# flyback.net
KiCad netlist of a schematic drawn in Altium Designer
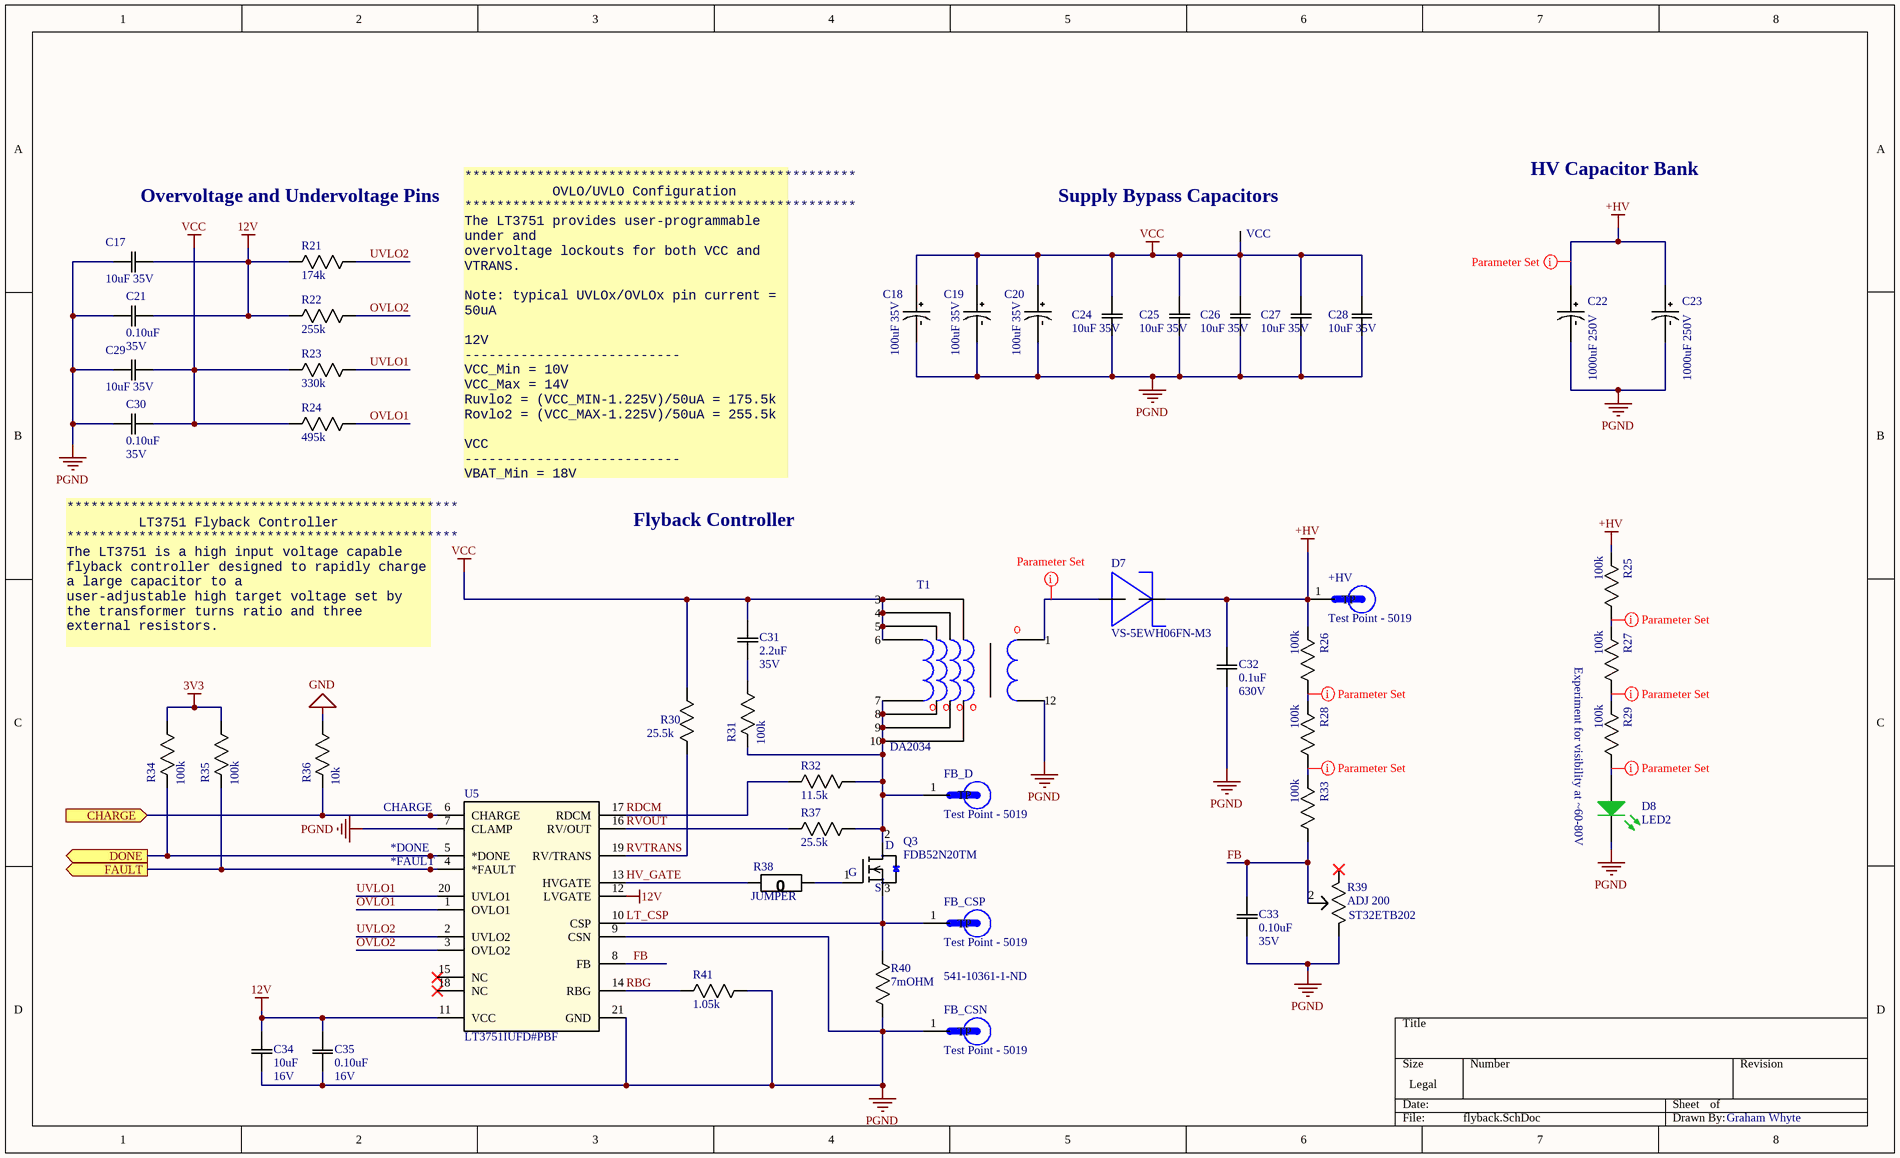
[diagram p0: flyback.SchDoc]

(export (version "E")
  (design (tool "Eeschema 10.0.6"))
  (components
    (comp (ref "*DONE")
      (value "Test Point (Via)")
      (footprint "TP")
      (libsource (lib "AltiumLibraries") (part "Test Point (Via)"))
    )
    (comp (ref "*FAULT")
      (value "Test Point (Via)")
      (footprint "TP")
      (libsource (lib "AltiumLibraries") (part "Test Point (Via)"))
    )
    (comp (ref "+HV")
      (value "Test Point - 5019")
      (footprint "TP380X203")
      (description "PC Test Point, Miniature Phosphor Bronze, Silver Plating Surface Mount Mounting Type")
      (fields (field (name "MP") "5019") (field (name "MF") "Keystone Electronics"))
      (libsource (lib "AltiumLibraries") (part "Test Point - 5019"))
    )
    (comp (ref "C17")
      (value "10uF 35V")
      (footprint "0805")
      (description "CAP CER 10uF 35V X5R 1206/0805")
      (fields (field (name "TOLERANCE") "10%"))
      (libsource (lib "AltiumLibraries") (part "CAP 10uF 35V"))
    )
    (comp (ref "C18")
      (value "100uF 35V")
      (footprint "CAP POL ALU 6.3x5.8")
      (description "CAP ALUM 100UF 35V SMD")
      (fields (field (name "TOLERANCE") "20%"))
      (libsource (lib "AltiumLibraries") (part "CAP POL 100uF SMD"))
    )
    (comp (ref "C19")
      (value "100uF 35V")
      (footprint "CAP POL ALU 6.3x5.8")
      (description "CAP ALUM 100UF 35V SMD")
      (fields (field (name "TOLERANCE") "20%"))
      (libsource (lib "AltiumLibraries") (part "CAP POL 100uF SMD"))
    )
    (comp (ref "C20")
      (value "100uF 35V")
      (footprint "CAP POL ALU 6.3x5.8")
      (description "CAP ALUM 100UF 35V SMD")
      (fields (field (name "TOLERANCE") "20%"))
      (libsource (lib "AltiumLibraries") (part "CAP POL 100uF SMD"))
    )
    (comp (ref "C21")
      (value "0.10uF")
      (footprint "0805")
      (description "CAP CER 0.10UF 35V X7R 0603/0805")
      (fields (field (name "TOLERANCE") "10%") (field (name "RATING") "35V"))
      (libsource (lib "AltiumLibraries") (part "CAP 0.10uF 35V"))
    )
    (comp (ref "C22")
      (value "1000uF 250V")
      (footprint "RADIAL, CAN - THRU 25.4mm")
      (description "United Chemi-Con\r\nESMQ251VSN102MQ45S")
      (fields
        (field (name "MANUFACTURER") "United Chemi-Con")
        (field (name "MANUFACTURER PART NUMBER") "ESMQ251VSN102MQ45S")
      )
      (libsource (lib "AltiumLibraries") (part "CAP POL 1000uF"))
    )
    (comp (ref "C23")
      (value "1000uF 250V")
      (footprint "RADIAL, CAN - THRU 25.4mm")
      (description "United Chemi-Con\r\nESMQ251VSN102MQ45S")
      (fields
        (field (name "MANUFACTURER") "United Chemi-Con")
        (field (name "MANUFACTURER PART NUMBER") "ESMQ251VSN102MQ45S")
      )
      (libsource (lib "AltiumLibraries") (part "CAP POL 1000uF"))
    )
    (comp (ref "C24")
      (value "10uF 35V")
      (footprint "0805")
      (description "CAP CER 10uF 35V X5R 1206/0805")
      (fields (field (name "TOLERANCE") "10%"))
      (libsource (lib "AltiumLibraries") (part "CAP 10uF 35V"))
    )
    (comp (ref "C25")
      (value "10uF 35V")
      (footprint "0805")
      (description "CAP CER 10uF 35V X5R 1206/0805")
      (fields (field (name "TOLERANCE") "10%"))
      (libsource (lib "AltiumLibraries") (part "CAP 10uF 35V"))
    )
    (comp (ref "C26")
      (value "10uF 35V")
      (footprint "0805")
      (description "CAP CER 10uF 35V X5R 1206/0805")
      (fields (field (name "TOLERANCE") "10%"))
      (libsource (lib "AltiumLibraries") (part "CAP 10uF 35V"))
    )
    (comp (ref "C27")
      (value "10uF 35V")
      (footprint "0805")
      (description "CAP CER 10uF 35V X5R 1206/0805")
      (fields (field (name "TOLERANCE") "10%"))
      (libsource (lib "AltiumLibraries") (part "CAP 10uF 35V"))
    )
    (comp (ref "C28")
      (value "10uF 35V")
      (footprint "0805")
      (description "CAP CER 10uF 35V X5R 1206/0805")
      (fields (field (name "TOLERANCE") "10%"))
      (libsource (lib "AltiumLibraries") (part "CAP 10uF 35V"))
    )
    (comp (ref "C29")
      (value "10uF 35V")
      (footprint "0805")
      (description "CAP CER 10uF 35V X5R 1206/0805")
      (fields (field (name "TOLERANCE") "10%"))
      (libsource (lib "AltiumLibraries") (part "CAP 10uF 35V"))
    )
    (comp (ref "C30")
      (value "0.10uF")
      (footprint "0805")
      (description "CAP CER 0.10UF 35V X7R 0603/0805")
      (fields (field (name "TOLERANCE") "10%") (field (name "RATING") "35V"))
      (libsource (lib "AltiumLibraries") (part "CAP 0.10uF 35V"))
    )
    (comp (ref "C31")
      (value "2.2uF")
      (footprint "0603")
      (description "CAP CER 2.2UF 35V X7R 0603/0805")
      (fields (field (name "TOLERANCE") "10%") (field (name "RATING") "35V"))
      (libsource (lib "AltiumLibraries") (part "CAP 2.2uF 35V"))
    )
    (comp (ref "C32")
      (value "0.1uF")
      (footprint "1210")
      (description "CAP CER 0.1uF 630V X7R 1210")
      (fields (field (name "TOLERANCE") "10%") (field (name "RATING") "630V"))
      (libsource (lib "AltiumLibraries") (part "CAP 0.1uF 630V"))
    )
    (comp (ref "C33")
      (value "0.10uF")
      (footprint "0805")
      (description "CAP CER 0.10UF 35V X7R 0603/0805")
      (fields (field (name "TOLERANCE") "10%") (field (name "RATING") "35V"))
      (libsource (lib "AltiumLibraries") (part "CAP 0.10uF 35V"))
    )
    (comp (ref "C34")
      (value "10uF")
      (footprint "0603")
      (description "CAP CER 10UF 16V X5R 0603/0805")
      (fields (field (name "TOLERANCE") "10%") (field (name "RATING") "16V"))
      (libsource (lib "AltiumLibraries") (part "CAP 10uF 16V"))
    )
    (comp (ref "C35")
      (value "0.10uF")
      (footprint "0603")
      (description "CAP CER 0.10UF 16V X5R 0603/0805")
      (fields (field (name "TOLERANCE") "10%") (field (name "RATING") "16V"))
      (libsource (lib "AltiumLibraries") (part "CAP 0.10uF 16V"))
    )
    (comp (ref "CHARGE")
      (value "Test Point (Via)")
      (footprint "TP")
      (libsource (lib "AltiumLibraries") (part "Test Point (Via)"))
    )
    (comp (ref "D7")
      (value "VS-5EWH06FN-M3")
      (footprint "DPAK (TO-252)")
      (description "Diode Switching 600V 5A DPAK")
      (fields (field (name "MF") "Vishay Diodes"))
      (libsource (lib "AltiumLibraries") (part "VS-5EWH06FN-M3"))
    )
    (comp (ref "D8")
      (value "LED2")
      (footprint "3.2X1.6X1.1")
      (description "Typical RED, GREEN, YELLOW, AMBER GaAs LED")
      (libsource (lib "AltiumLibraries") (part "LED GREEN SMD"))
    )
    (comp (ref "FB_CSN")
      (value "Test Point - 5019")
      (footprint "TP380X203")
      (description "PC Test Point, Miniature Phosphor Bronze, Silver Plating Surface Mount Mounting Type")
      (fields (field (name "MP") "5019") (field (name "MF") "Keystone Electronics"))
      (libsource (lib "AltiumLibraries") (part "Test Point - 5019"))
    )
    (comp (ref "FB_CSP")
      (value "Test Point - 5019")
      (footprint "TP380X203")
      (description "PC Test Point, Miniature Phosphor Bronze, Silver Plating Surface Mount Mounting Type")
      (fields (field (name "MP") "5019") (field (name "MF") "Keystone Electronics"))
      (libsource (lib "AltiumLibraries") (part "Test Point - 5019"))
    )
    (comp (ref "FB_D")
      (value "Test Point - 5019")
      (footprint "TP380X203")
      (description "PC Test Point, Miniature Phosphor Bronze, Silver Plating Surface Mount Mounting Type")
      (fields (field (name "MP") "5019") (field (name "MF") "Keystone Electronics"))
      (libsource (lib "AltiumLibraries") (part "Test Point - 5019"))
    )
    (comp (ref "Q3")
      (value "FDB52N20TM")
      (footprint "D2PAK (TO-263) (2)")
      (description "N-Channel 200 V 52A (Tc) 357W (Tc) Surface Mount D²PAK (TO-263)")
      (libsource (lib "AltiumLibraries") (part "MOSFET N-CH FDB52N20TM"))
    )
    (comp (ref "R21")
      (value "174k")
      (footprint "0603")
      (description "RES SMD 174K OHM 1% 1/8W 0805/0603")
      (fields
        (field (name "MANUFACTURER") "Yageo")
        (field (name "MANUFACTURER PART NUMBER") "RC0805FR-07174KL")
      )
      (libsource (lib "AltiumLibraries") (part "RES 174k 1/8W"))
    )
    (comp (ref "R22")
      (value "255k")
      (footprint "0603")
      (description "0805/0603 Resistor, 6A, 0.125W, 25ppm, 0.1%, 255K")
      (libsource (lib "AltiumLibraries") (part "RES 255k 1/8W - 5%"))
    )
    (comp (ref "R23")
      (value "330k")
      (footprint "0603")
      (description "RES SMD 330K OHM 1% 1/8W 0805/0603")
      (libsource (lib "AltiumLibraries") (part "RES 330k 1/8W - 1%"))
    )
    (comp (ref "R24")
      (value "495k")
      (footprint "0603")
      (description "RES SMD 495K OHM 1% 1/8W 0805/0603")
      (fields
        (field (name "MANUFACTURER") "Yageo")
        (field (name "MANUFACTURER PART NUMBER") "RC0805FR-07499KL")
      )
      (libsource (lib "AltiumLibraries") (part "RES 495k 1/8W"))
    )
    (comp (ref "R25")
      (value "100k")
      (footprint "0603")
      (description "RES SMD 100K OHM 5% 1/8W 0805/0603")
      (fields (field (name "TOLERANCE") "5%"))
      (libsource (lib "") (part "RES 100k 1/8W - 5%_1"))
    )
    (comp (ref "R26")
      (value "100k")
      (footprint "0603")
      (description "RES SMD 100K OHM 1% 1/8W 0805/0603")
      (fields (field (name "TOLERANCE") "1%"))
      (libsource (lib "AltiumLibraries") (part "RES 100k 1/8W - 1%"))
    )
    (comp (ref "R27")
      (value "100k")
      (footprint "0603")
      (description "RES SMD 100K OHM 5% 1/8W 0805/0603")
      (fields (field (name "TOLERANCE") "5%"))
      (libsource (lib "AltiumLibraries") (part "RES 100k 1/8W - 5%"))
    )
    (comp (ref "R28")
      (value "100k")
      (footprint "0603")
      (description "RES SMD 100K OHM 1% 1/8W 0805/0603")
      (fields (field (name "TOLERANCE") "1%"))
      (libsource (lib "") (part "RES 100k 1/8W - 1%_1"))
    )
    (comp (ref "R29")
      (value "100k")
      (footprint "0603")
      (description "RES SMD 100K OHM 5% 1/8W 0805/0603")
      (fields (field (name "TOLERANCE") "5%"))
      (libsource (lib "AltiumLibraries") (part "RES 100k 1/8W - 5%"))
    )
    (comp (ref "R30")
      (value "25.5k")
      (footprint "0603")
      (description "RES SMD 25.5K OHM 0.1% 1/8W 0805/0603")
      (fields
        (field (name "MANUFACTURER") "Panasonic")
        (field (name "MANUFACTURER PART NUMBER") "ERA-6AEB2552V")
      )
      (libsource (lib "AltiumLibraries") (part "RES 25.5k 1/8W"))
    )
    (comp (ref "R31")
      (value "100k")
      (footprint "0603")
      (description "RES SMD 100K OHM 1% 1/8W 0805/0603")
      (fields (field (name "TOLERANCE") "1%"))
      (libsource (lib "AltiumLibraries") (part "RES 100k 1/8W - 1%"))
    )
    (comp (ref "R32")
      (value "11.5k")
      (footprint "0603")
      (description "RES SMD 11.5K OHM 0.1% 1/8W 0805 Thin Film")
      (fields
        (field (name "MANUFACTURER") "Panasonic")
        (field (name "MANUFACTURER PART NUMBER") "ERA-6AEB1152V")
      )
      (libsource (lib "AltiumLibraries") (part "RES 11.5k 1/8W"))
    )
    (comp (ref "R33")
      (value "100k")
      (footprint "0603")
      (description "RES SMD 100K OHM 1% 1/8W 0805/0603")
      (fields (field (name "TOLERANCE") "1%"))
      (libsource (lib "") (part "RES 100k 1/8W - 1%_1"))
    )
    (comp (ref "R34")
      (value "100k")
      (footprint "0603")
      (description "RES SMD 100K OHM 5% 1/8W 0805/0603")
      (fields (field (name "TOLERANCE") "5%"))
      (libsource (lib "AltiumLibraries") (part "RES 100k 1/8W - 5%"))
    )
    (comp (ref "R35")
      (value "100k")
      (footprint "0603")
      (description "RES SMD 100K OHM 5% 1/8W 0805/0603")
      (fields (field (name "TOLERANCE") "5%"))
      (libsource (lib "AltiumLibraries") (part "RES 100k 1/8W - 5%"))
    )
    (comp (ref "R36")
      (value "10k")
      (footprint "0603")
      (description "RES SMD 10K OHM 5% 1/8W 0805/0603")
      (fields (field (name "TOLERANCE") "5%"))
      (libsource (lib "AltiumLibraries") (part "RES 10k 1/8W - 5%"))
    )
    (comp (ref "R37")
      (value "25.5k")
      (footprint "0603")
      (description "RES SMD 25.5K OHM 0.1% 1/8W 0805/0603")
      (fields
        (field (name "MANUFACTURER") "Panasonic")
        (field (name "MANUFACTURER PART NUMBER") "ERA-6AEB2552V")
      )
      (libsource (lib "AltiumLibraries") (part "RES 25.5k 1/8W"))
    )
    (comp (ref "R38")
      (value "JUMPER")
      (footprint "0603")
      (description "RES SMD 0 OHM JUMPER GENERIC 0805/0603")
      (libsource (lib "AltiumLibraries") (part "RES 0 JUMPER"))
    )
    (comp (ref "R39")
      (value "ADJ 200")
      (footprint "POT SMD")
      (description "SMD Potentiometer 200Ohm Range")
      (libsource (lib "AltiumLibraries") (part "RES POT 200"))
    )
    (comp (ref "R40")
      (value "7mOHM")
      (footprint "2512")
      (description "RES SMD 7m OHM 1% 3W 2512")
      (fields
        (field (name "TOLERANCE") "1%")
        (field (name "MFG") "VISHAY")
        (field (name "SUPPLIER PART NUMBER 1") "541-10361-1-ND")
      )
      (libsource (lib "AltiumLibraries") (part "RES 7m 3W"))
    )
    (comp (ref "R41")
      (value "1.05k")
      (footprint "0603")
      (description "RES SMD 1.05K OHM 0.1% 1/8W 0805/0603")
      (fields (field (name "TOLERANCE") "0.1%"))
      (libsource (lib "AltiumLibraries") (part "RES 1.05k 1/8W"))
    )
    (comp (ref "T1")
      (value "DA2034")
      (footprint "DA2034")
      (description "Audio Transformers / Signal Transformers DA2032 Cap Chrgr For Linear LT3750/51")
      (libsource (lib "AltiumLibraries") (part "DA2034"))
    )
    (comp (ref "U5")
      (value "LT3751IUFD#PBF")
      (footprint "QFN-20_UFD_LIT-M")
      (description "Photoflash Capacitor Charger PMIC 20-QFN (4x5)")
      (fields
        (field (name "MANUFACTURER_PART_NUMBER") "lt3751iufd#pbf")
        (field (name "COPYRIGHT") "Copyright (C) 2021 Ultra Librarian. All rights reserved.")
      )
      (libsource (lib "AltiumLibraries") (part "LT3751IUFD#PBF"))
    )
    (comp (ref "VCC")
      (value "Test Point (Via)")
      (footprint "TP")
      (libsource (lib "AltiumLibraries") (part "Test Point (Via)"))
    )
  )
  (nets
    (net (code "1") (name "+HV") (class "Default")
      (node (ref "+HV") (pin "1") (pinfunction "TP_1") (pintype "passive"))
      (node (ref "C22") (pin "POS") (pinfunction "POS_POS") (pintype "passive"))
      (node (ref "C23") (pin "POS") (pinfunction "POS_POS") (pintype "passive"))
      (node (ref "C32") (pin "1") (pinfunction "C1_1") (pintype "passive"))
      (node (ref "D7") (pin "OUT") (pinfunction "OUT_OUT") (pintype "passive"))
      (node (ref "R25") (pin "2") (pinfunction "R2_2") (pintype "passive"))
      (node (ref "R26") (pin "2") (pinfunction "R2_2") (pintype "passive"))
    )
    (net (code "3") (name "/CHARGE") (class "Default")
      (node (ref "CHARGE") (pin "1") (pinfunction "1_1") (pintype "passive"))
      (node (ref "R36") (pin "2") (pinfunction "R2_2") (pintype "passive"))
      (node (ref "U5") (pin "6") (pinfunction "CHARGE_6") (pintype "passive"))
    )
    (net (code "4") (name "/DONE") (class "Default")
      (node (ref "*DONE") (pin "1") (pinfunction "1_1") (pintype "passive"))
      (node (ref "R34") (pin "2") (pinfunction "R2_2") (pintype "passive"))
      (node (ref "U5") (pin "5") (pinfunction "*DONE_5") (pintype "passive"))
    )
    (net (code "5") (name "/FAULT") (class "Default")
      (node (ref "*FAULT") (pin "1") (pinfunction "1_1") (pintype "passive"))
      (node (ref "R35") (pin "2") (pinfunction "R2_2") (pintype "passive"))
      (node (ref "U5") (pin "4") (pinfunction "*FAULT_4") (pintype "passive"))
    )
    (net (code "6") (name "/FB") (class "Default")
      (node (ref "C33") (pin "1") (pinfunction "C1_1") (pintype "passive"))
      (node (ref "R33") (pin "1") (pinfunction "R1_1") (pintype "passive"))
      (node (ref "R39") (pin "2") (pinfunction "2_2") (pintype "passive"))
      (node (ref "U5") (pin "8") (pinfunction "FB_8") (pintype "passive"))
    )
    (net (code "7") (name "/HV_GATE") (class "Default")
      (node (ref "R38") (pin "2") (pinfunction "R2_2") (pintype "passive"))
      (node (ref "U5") (pin "13") (pinfunction "HVGATE_13") (pintype "passive"))
    )
    (net (code "8") (name "/LT_CSP") (class "Default")
      (node (ref "FB_CSP") (pin "1") (pinfunction "TP_1") (pintype "passive"))
      (node (ref "Q3") (pin "3") (pinfunction "S_3") (pintype "passive"))
      (node (ref "R40") (pin "2") (pinfunction "R2_2") (pintype "passive"))
      (node (ref "U5") (pin "10") (pinfunction "CSP_10") (pintype "passive"))
    )
    (net (code "9") (name "/OVLO1") (class "Default")
      (node (ref "R24") (pin "1") (pinfunction "R1_1") (pintype "passive"))
      (node (ref "U5") (pin "1") (pinfunction "OVLO1_1") (pintype "passive"))
    )
    (net (code "10") (name "/OVLO2") (class "Default")
      (node (ref "R22") (pin "1") (pinfunction "R1_1") (pintype "passive"))
      (node (ref "U5") (pin "3") (pinfunction "OVLO2_3") (pintype "passive"))
    )
    (net (code "11") (name "/RBG") (class "Default")
      (node (ref "R41") (pin "2") (pinfunction "R2_2") (pintype "passive"))
      (node (ref "U5") (pin "14") (pinfunction "RBG_14") (pintype "passive"))
    )
    (net (code "12") (name "/RDCM") (class "Default")
      (node (ref "R32") (pin "2") (pinfunction "R2_2") (pintype "passive"))
      (node (ref "U5") (pin "17") (pinfunction "RDCM_17") (pintype "passive"))
    )
    (net (code "13") (name "/RVOUT") (class "Default")
      (node (ref "R37") (pin "2") (pinfunction "R2_2") (pintype "passive"))
      (node (ref "U5") (pin "16") (pinfunction "RV/OUT_16") (pintype "passive"))
    )
    (net (code "14") (name "/RVTRANS") (class "Default")
      (node (ref "R30") (pin "2") (pinfunction "R2_2") (pintype "passive"))
      (node (ref "U5") (pin "19") (pinfunction "RV/TRANS_19") (pintype "passive"))
    )
    (net (code "15") (name "/UVLO1") (class "Default")
      (node (ref "R23") (pin "1") (pinfunction "R1_1") (pintype "passive"))
      (node (ref "U5") (pin "20") (pinfunction "UVLO1_20") (pintype "passive"))
    )
    (net (code "16") (name "/UVLO2") (class "Default")
      (node (ref "R21") (pin "1") (pinfunction "R1_1") (pintype "passive"))
      (node (ref "U5") (pin "2") (pinfunction "UVLO2_2") (pintype "passive"))
    )
    (net (code "17") (name "3V3") (class "Default")
      (node (ref "R34") (pin "1") (pinfunction "R1_1") (pintype "passive"))
      (node (ref "R35") (pin "1") (pinfunction "R1_1") (pintype "passive"))
    )
    (net (code "18") (name "12V") (class "Default")
      (node (ref "C17") (pin "2") (pinfunction "C2_2") (pintype "passive"))
      (node (ref "C21") (pin "2") (pinfunction "C2_2") (pintype "passive"))
      (node (ref "C34") (pin "1") (pinfunction "C1_1") (pintype "passive"))
      (node (ref "C35") (pin "2") (pinfunction "C2_2") (pintype "passive"))
      (node (ref "R21") (pin "2") (pinfunction "R2_2") (pintype "passive"))
      (node (ref "R22") (pin "2") (pinfunction "R2_2") (pintype "passive"))
      (node (ref "U5") (pin "11") (pinfunction "VCC_11") (pintype "power_in"))
      (node (ref "U5") (pin "12") (pinfunction "LVGATE_12") (pintype "passive"))
    )
    (net (code "19") (name "GND") (class "Default")
      (node (ref "R36") (pin "1") (pinfunction "R1_1") (pintype "passive"))
    )
    (net (code "20") (name "Net-(C31-C1)") (class "Default")
      (node (ref "C31") (pin "1") (pinfunction "C1_1") (pintype "passive"))
      (node (ref "R31") (pin "1") (pinfunction "R1_1") (pintype "passive"))
    )
    (net (code "21") (name "Net-(D7-PadIN)") (class "Default")
      (node (ref "D7") (pin "IN") (pinfunction "IN_IN") (pintype "passive"))
      (node (ref "T1") (pin "1") (pinfunction "1_1") (pintype "passive"))
    )
    (net (code "22") (name "Net-(D8-A)") (class "Default")
      (node (ref "D8") (pin "1") (pinfunction "A_1") (pintype "passive"))
      (node (ref "R29") (pin "1") (pinfunction "R1_1") (pintype "passive"))
    )
    (net (code "23") (name "Net-(FB_D-TP)") (class "Default")
      (node (ref "FB_D") (pin "1") (pinfunction "TP_1") (pintype "passive"))
      (node (ref "Q3") (pin "2") (pinfunction "D_2") (pintype "passive"))
      (node (ref "R31") (pin "2") (pinfunction "R2_2") (pintype "passive"))
      (node (ref "R32") (pin "1") (pinfunction "R1_1") (pintype "passive"))
      (node (ref "R37") (pin "1") (pinfunction "R1_1") (pintype "passive"))
      (node (ref "T1") (pin "10") (pinfunction "10_10") (pintype "passive"))
      (node (ref "T1") (pin "7") (pinfunction "7_7") (pintype "passive"))
      (node (ref "T1") (pin "8") (pinfunction "8_8") (pintype "passive"))
      (node (ref "T1") (pin "9") (pinfunction "9_9") (pintype "passive"))
    )
    (net (code "24") (name "Net-(Q3-G)") (class "Default")
      (node (ref "Q3") (pin "1") (pinfunction "G_1") (pintype "passive"))
      (node (ref "R38") (pin "1") (pinfunction "R1_1") (pintype "passive"))
    )
    (net (code "25") (name "Net-(R25-R1)") (class "Default")
      (node (ref "R25") (pin "1") (pinfunction "R1_1") (pintype "passive"))
      (node (ref "R27") (pin "2") (pinfunction "R2_2") (pintype "passive"))
    )
    (net (code "26") (name "Net-(R26-R1)") (class "Default")
      (node (ref "R26") (pin "1") (pinfunction "R1_1") (pintype "passive"))
      (node (ref "R28") (pin "2") (pinfunction "R2_2") (pintype "passive"))
    )
    (net (code "27") (name "Net-(R27-R1)") (class "Default")
      (node (ref "R27") (pin "1") (pinfunction "R1_1") (pintype "passive"))
      (node (ref "R29") (pin "2") (pinfunction "R2_2") (pintype "passive"))
    )
    (net (code "28") (name "Net-(R28-R1)") (class "Default")
      (node (ref "R28") (pin "1") (pinfunction "R1_1") (pintype "passive"))
      (node (ref "R33") (pin "2") (pinfunction "R2_2") (pintype "passive"))
    )
    (net (code "29") (name "PGND") (class "Default")
      (node (ref "C17") (pin "1") (pinfunction "C1_1") (pintype "passive"))
      (node (ref "C18") (pin "NEG") (pinfunction "NEG_NEG") (pintype "passive"))
      (node (ref "C19") (pin "NEG") (pinfunction "NEG_NEG") (pintype "passive"))
      (node (ref "C20") (pin "NEG") (pinfunction "NEG_NEG") (pintype "passive"))
      (node (ref "C21") (pin "1") (pinfunction "C1_1") (pintype "passive"))
      (node (ref "C22") (pin "NEG") (pinfunction "NEG_NEG") (pintype "passive"))
      (node (ref "C23") (pin "NEG") (pinfunction "NEG_NEG") (pintype "passive"))
      (node (ref "C24") (pin "1") (pinfunction "C1_1") (pintype "passive"))
      (node (ref "C25") (pin "1") (pinfunction "C1_1") (pintype "passive"))
      (node (ref "C26") (pin "1") (pinfunction "C1_1") (pintype "passive"))
      (node (ref "C27") (pin "1") (pinfunction "C1_1") (pintype "passive"))
      (node (ref "C28") (pin "1") (pinfunction "C1_1") (pintype "passive"))
      (node (ref "C29") (pin "1") (pinfunction "C1_1") (pintype "passive"))
      (node (ref "C30") (pin "1") (pinfunction "C1_1") (pintype "passive"))
      (node (ref "C32") (pin "2") (pinfunction "C2_2") (pintype "passive"))
      (node (ref "C33") (pin "2") (pinfunction "C2_2") (pintype "passive"))
      (node (ref "C34") (pin "2") (pinfunction "C2_2") (pintype "passive"))
      (node (ref "C35") (pin "1") (pinfunction "C1_1") (pintype "passive"))
      (node (ref "D8") (pin "2") (pinfunction "K_2") (pintype "passive"))
      (node (ref "FB_CSN") (pin "1") (pinfunction "TP_1") (pintype "passive"))
      (node (ref "R39") (pin "3") (pinfunction "3_3") (pintype "passive"))
      (node (ref "R40") (pin "1") (pinfunction "R1_1") (pintype "passive"))
      (node (ref "R41") (pin "1") (pinfunction "R1_1") (pintype "passive"))
      (node (ref "T1") (pin "12") (pinfunction "12_12") (pintype "passive"))
      (node (ref "U5") (pin "21") (pinfunction "GND_21") (pintype "passive"))
      (node (ref "U5") (pin "7") (pinfunction "CLAMP_7") (pintype "passive"))
      (node (ref "U5") (pin "9") (pinfunction "CSN_9") (pintype "passive"))
    )
    (net (code "30") (name "VCC") (class "Default")
      (node (ref "C18") (pin "POS") (pinfunction "POS_POS") (pintype "passive"))
      (node (ref "C19") (pin "POS") (pinfunction "POS_POS") (pintype "passive"))
      (node (ref "C20") (pin "POS") (pinfunction "POS_POS") (pintype "passive"))
      (node (ref "C24") (pin "2") (pinfunction "C2_2") (pintype "passive"))
      (node (ref "C25") (pin "2") (pinfunction "C2_2") (pintype "passive"))
      (node (ref "C26") (pin "2") (pinfunction "C2_2") (pintype "passive"))
      (node (ref "C27") (pin "2") (pinfunction "C2_2") (pintype "passive"))
      (node (ref "C28") (pin "2") (pinfunction "C2_2") (pintype "passive"))
      (node (ref "C29") (pin "2") (pinfunction "C2_2") (pintype "passive"))
      (node (ref "C30") (pin "2") (pinfunction "C2_2") (pintype "passive"))
      (node (ref "C31") (pin "2") (pinfunction "C2_2") (pintype "passive"))
      (node (ref "R23") (pin "2") (pinfunction "R2_2") (pintype "passive"))
      (node (ref "R24") (pin "2") (pinfunction "R2_2") (pintype "passive"))
      (node (ref "R30") (pin "1") (pinfunction "R1_1") (pintype "passive"))
      (node (ref "T1") (pin "3") (pinfunction "3_3") (pintype "passive"))
      (node (ref "T1") (pin "4") (pinfunction "4_4") (pintype "passive"))
      (node (ref "T1") (pin "5") (pinfunction "5_5") (pintype "passive"))
      (node (ref "T1") (pin "6") (pinfunction "6_6") (pintype "passive"))
      (node (ref "VCC") (pin "1") (pinfunction "1_1") (pintype "passive"))
    )
    (net (code "31") (name "unconnected-(R39-Pad1)") (class "Default")
      (node (ref "R39") (pin "1") (pinfunction "1_1") (pintype "passive+no_connect"))
    )
    (net (code "32") (name "unconnected-(U5-NC-Pad15)") (class "Default")
      (node (ref "U5") (pin "15") (pinfunction "NC_15") (pintype "passive+no_connect"))
    )
    (net (code "33") (name "unconnected-(U5-NC-Pad18)") (class "Default")
      (node (ref "U5") (pin "18") (pinfunction "NC_18") (pintype "passive+no_connect"))
    )
  )
)
